# final.net
KiCad netlist of a schematic drawn in EAGLE
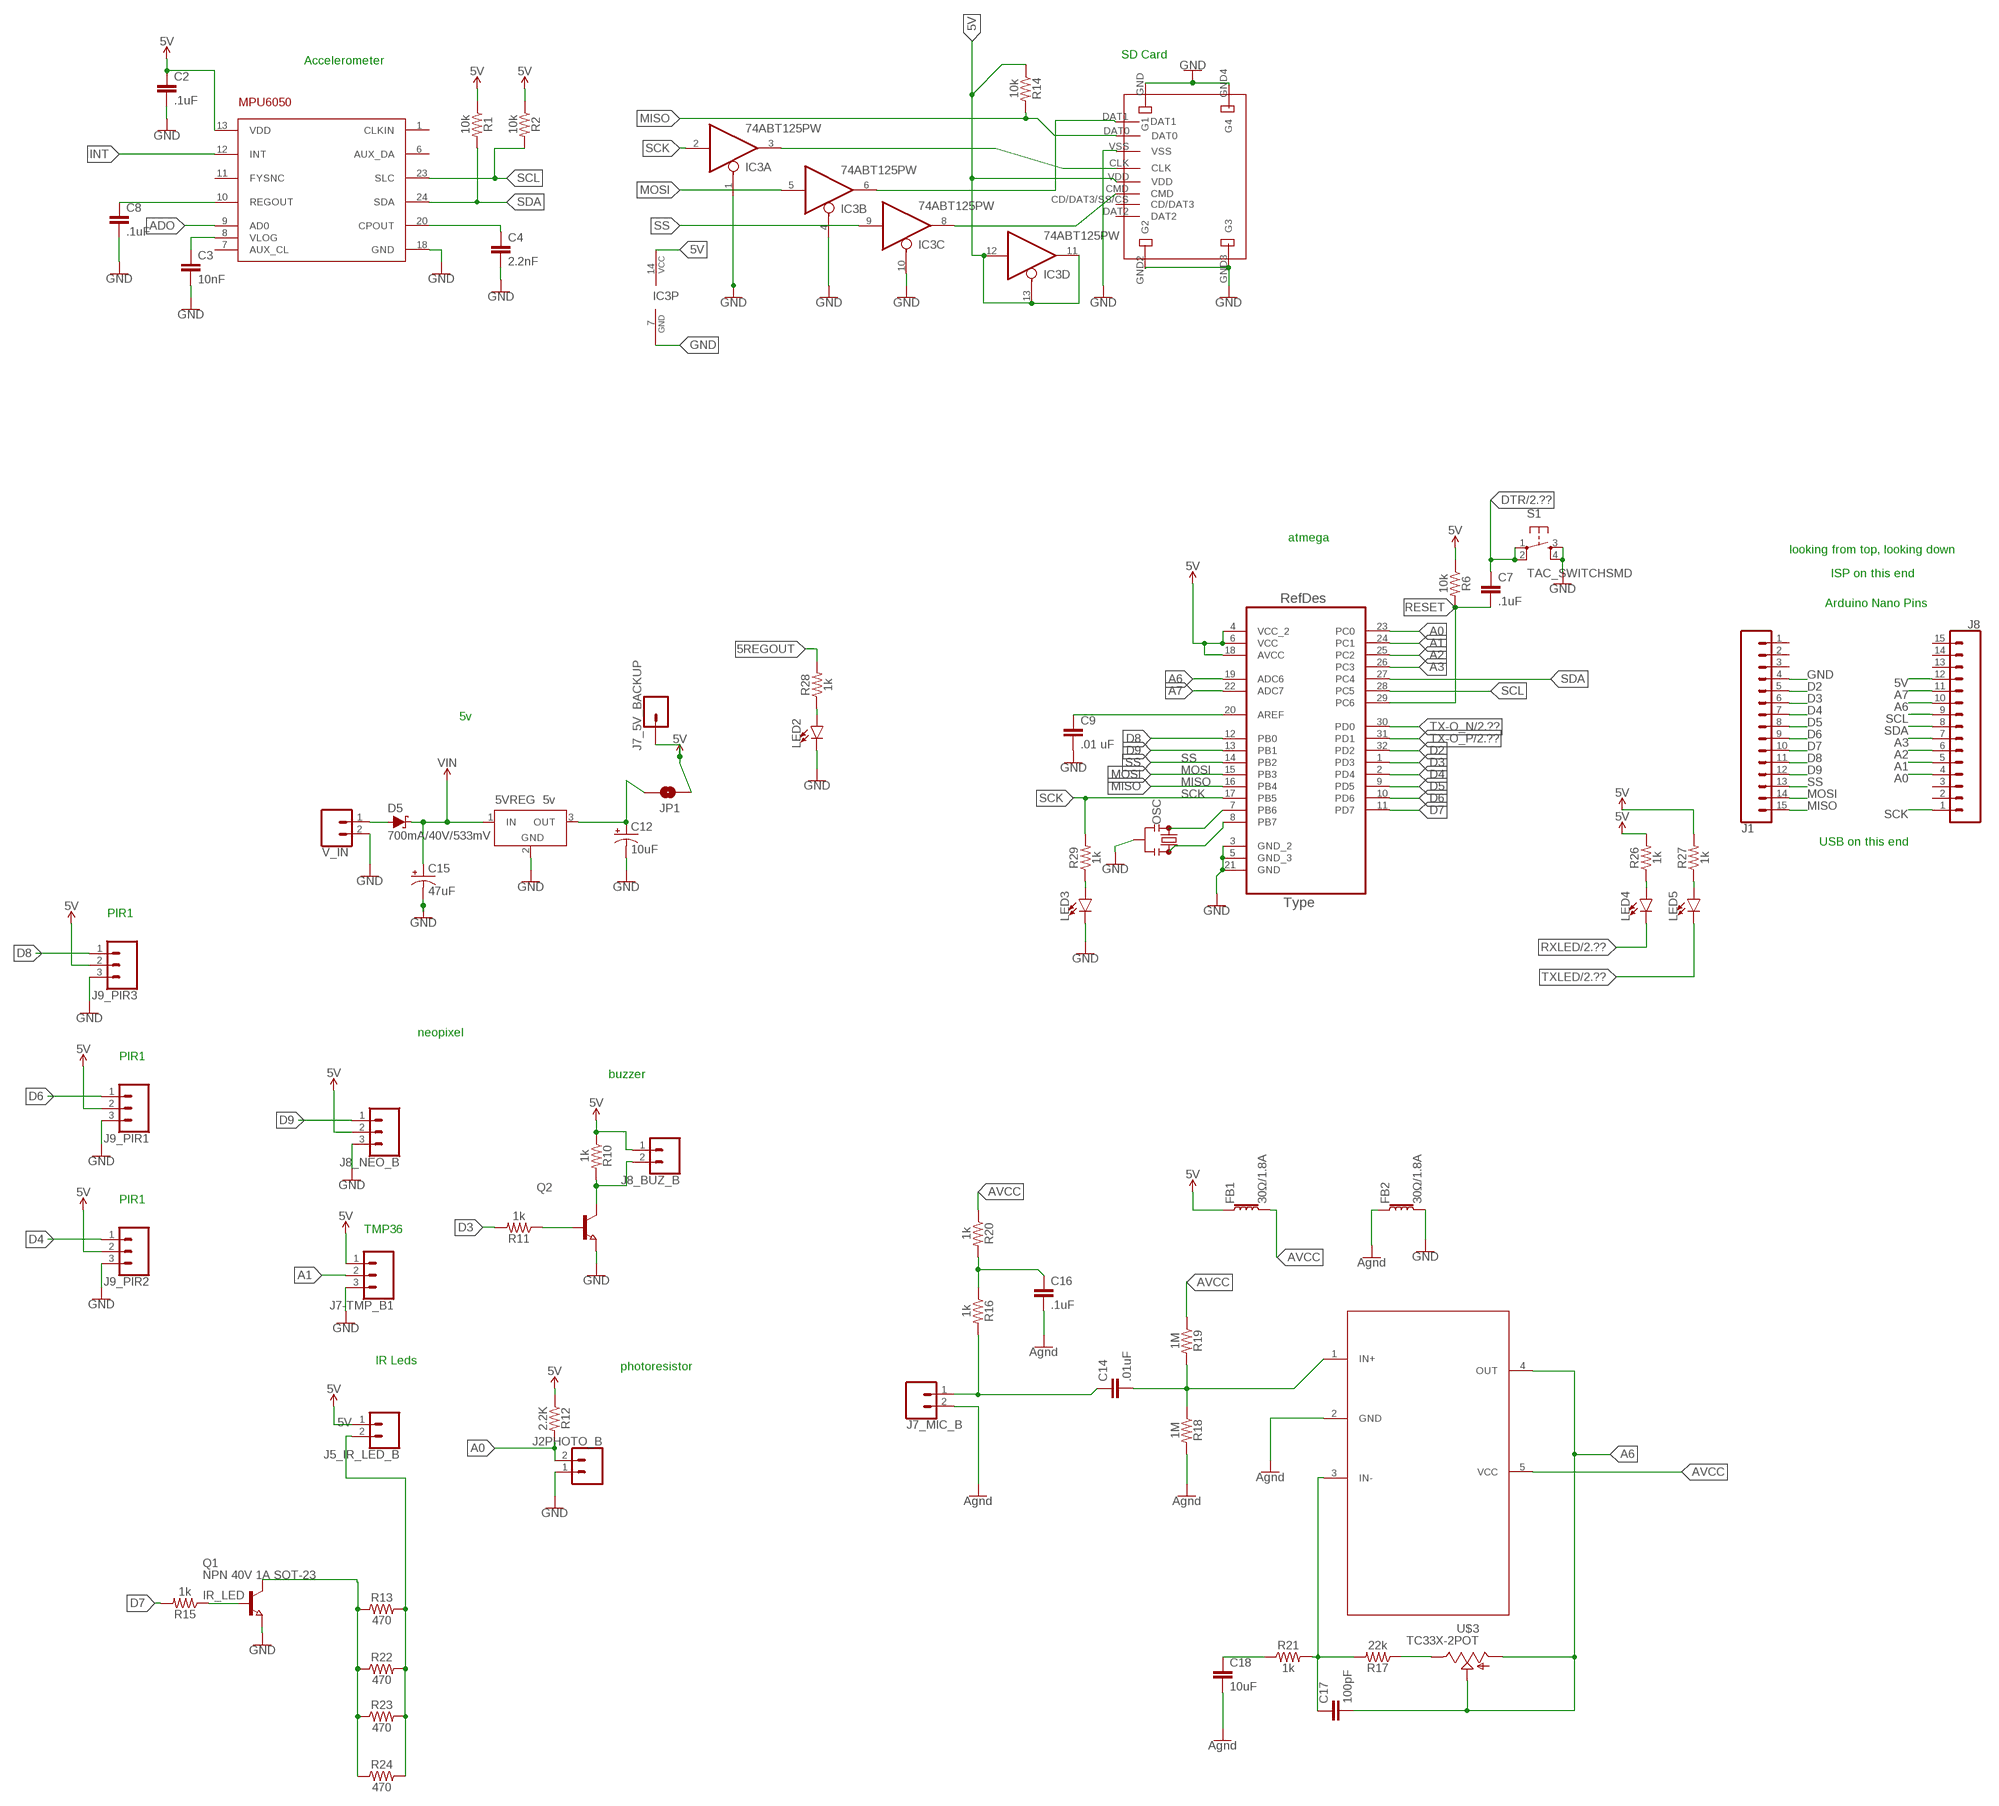
[diagram p0: schematic, sheet 1]
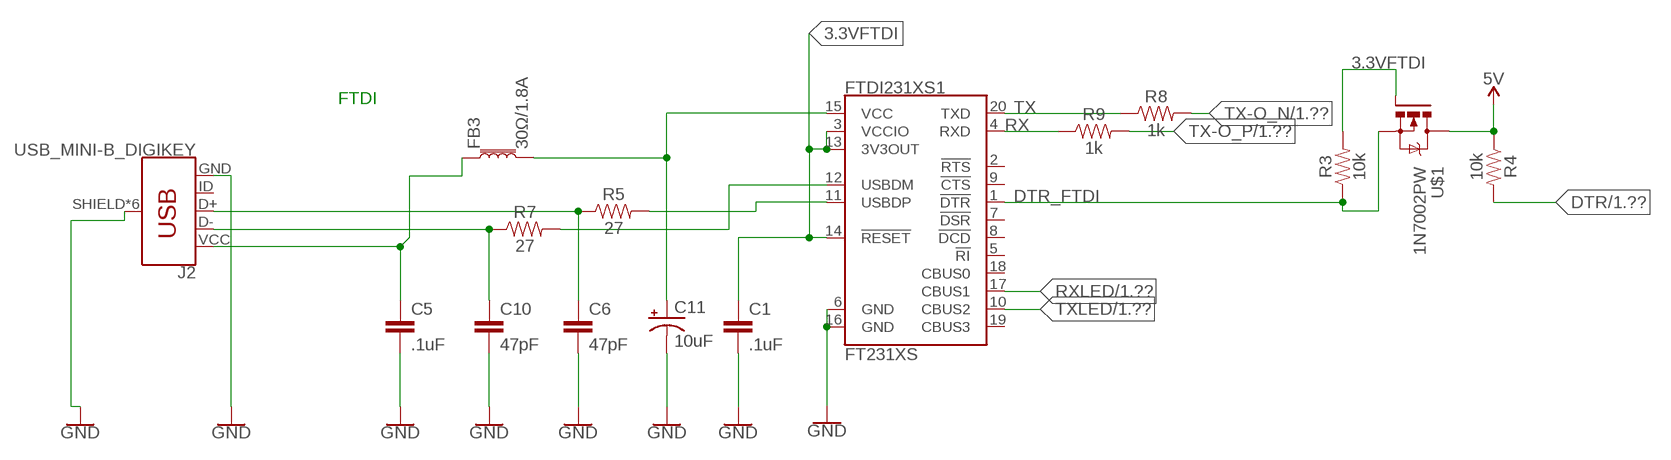
[diagram p1: schematic, sheet 2]

(export (version "E")
  (design (tool "Eeschema 10.0.6"))
  (components
    (comp (ref "C1")
      (value ".1uF")
      (footprint "eagle-import:0402-CAP")
      (libsource (lib "eagle-import") (part ".22UF-CER"))
    )
    (comp (ref "C5")
      (value ".1uF")
      (footprint "eagle-import:0402-CAP")
      (libsource (lib "eagle-import") (part ".22UF-CER"))
    )
    (comp (ref "C6")
      (value "47pF")
      (footprint "eagle-import:0402-CAP")
      (libsource (lib "eagle-import") (part ".22UF-CER"))
    )
    (comp (ref "C10")
      (value "47pF")
      (footprint "eagle-import:0402-CAP")
      (libsource (lib "eagle-import") (part ".22UF-CER"))
    )
    (comp (ref "C11")
      (value "10uF")
      (footprint "eagle-import:EIA3216")
      (libsource (lib "eagle-import") (part "10UF-TANT"))
    )
    (comp (ref "FB3")
      (value "30Ω/1.8A")
      (footprint "eagle-import:0603")
      (libsource (lib "eagle-import") (part "FERRITE_BEAD-0603"))
    )
    (comp (ref "FTDI231XS1")
      (value "FT231XS")
      (footprint "eagle-import:SSOP20_L")
      (libsource (lib "eagle-import") (part "FT231XS"))
    )
    (comp (ref "J2")
      (value "USB_MINI-B_DIGIKEY")
      (footprint "eagle-import:MICRO-USB-DIGIKEY-FCI2")
      (libsource (lib "eagle-import") (part "USB_MINI-B_DIGIKEY"))
    )
    (comp (ref "R3")
      (value "10k")
      (footprint "eagle-import:0603")
      (libsource (lib "eagle-import") (part "0.05OHM-0603-1/5W-1%"))
    )
    (comp (ref "R4")
      (value "10k")
      (footprint "eagle-import:0603")
      (libsource (lib "eagle-import") (part "0.05OHM-0603-1/5W-1%"))
    )
    (comp (ref "R5")
      (value "27")
      (footprint "eagle-import:0603")
      (libsource (lib "eagle-import") (part "0.05OHM-0603-1/5W-1%"))
    )
    (comp (ref "R7")
      (value "27")
      (footprint "eagle-import:0603")
      (libsource (lib "eagle-import") (part "0.05OHM-0603-1/5W-1%"))
    )
    (comp (ref "R8")
      (value "1k")
      (footprint "eagle-import:0603")
      (libsource (lib "eagle-import") (part "0.05OHM-0603-1/5W-1%"))
    )
    (comp (ref "R9")
      (value "1k")
      (footprint "eagle-import:0603")
      (libsource (lib "eagle-import") (part "0.05OHM-0603-1/5W-1%"))
    )
    (comp (ref "U$1")
      (value "1N7002PW")
      (footprint "eagle-import:SOT323W_INFINEON")
      (libsource (lib "eagle-import") (part "1N7002PW"))
    )
    (comp (ref "5VREG")
      (value "5v")
      (footprint "eagle-import:SOT223")
      (fields (field (name "MPN") "LT1129CST-5#PBF"))
      (libsource (lib "eagle-import") (part "LT1129CST5"))
    )
    (comp (ref "ATMEGA328P-AU")
      (value "ATMEGA328P-AU")
      (footprint "eagle-import:QFP80P900X900X120-32N")
      (libsource (lib "eagle-import") (part "ATMEGA328P-AU"))
    )
    (comp (ref "C2")
      (value ".1uF")
      (footprint "eagle-import:0402-CAP")
      (libsource (lib "eagle-import") (part ".22UF-CER"))
    )
    (comp (ref "C3")
      (value "10nF")
      (footprint "eagle-import:0402-CAP")
      (libsource (lib "eagle-import") (part ".22UF-CER"))
    )
    (comp (ref "C4")
      (value "2.2nF")
      (footprint "eagle-import:0402-CAP")
      (libsource (lib "eagle-import") (part ".22UF-CER"))
    )
    (comp (ref "C7")
      (value ".1uF")
      (footprint "eagle-import:0402-CAP")
      (libsource (lib "eagle-import") (part ".22UF-CER"))
    )
    (comp (ref "C8")
      (value ".1uF")
      (footprint "eagle-import:0402-CAP")
      (libsource (lib "eagle-import") (part ".22UF-CER"))
    )
    (comp (ref "C9")
      (value ".01 uF")
      (footprint "eagle-import:0402-CAP")
      (libsource (lib "eagle-import") (part ".22UF-CER"))
    )
    (comp (ref "C12")
      (value "10uF")
      (footprint "eagle-import:EIA3216")
      (libsource (lib "eagle-import") (part "10UF-TANT"))
    )
    (comp (ref "C14")
      (value ".01uF")
      (footprint "eagle-import:0402-CAP")
      (libsource (lib "eagle-import") (part ".22UF-CER"))
    )
    (comp (ref "C15")
      (value "47uF")
      (footprint "eagle-import:EIA3216")
      (libsource (lib "eagle-import") (part "10UF-TANT"))
    )
    (comp (ref "C16")
      (value ".1uF")
      (footprint "eagle-import:0402-CAP")
      (libsource (lib "eagle-import") (part ".22UF-CER"))
    )
    (comp (ref "C17")
      (value "100pF")
      (footprint "eagle-import:0402-CAP")
      (libsource (lib "eagle-import") (part ".22UF-CER"))
    )
    (comp (ref "C18")
      (value "10uF")
      (footprint "eagle-import:0402-CAP")
      (libsource (lib "eagle-import") (part ".22UF-CER"))
    )
    (comp (ref "D5")
      (value "700mA/40V/533mV")
      (footprint "eagle-import:SOT23-3")
      (libsource (lib "eagle-import") (part "DIODE-SCHOTTKY-ZLLS500"))
    )
    (comp (ref "FB1")
      (value "30Ω/1.8A")
      (footprint "eagle-import:0603")
      (libsource (lib "eagle-import") (part "FERRITE_BEAD-0603"))
    )
    (comp (ref "FB2")
      (value "30Ω/1.8A")
      (footprint "eagle-import:0603")
      (libsource (lib "eagle-import") (part "FERRITE_BEAD-0603"))
    )
    (comp (ref "IC3")
      (value "74ABT125PW")
      (footprint "eagle-import:TSSOP14")
      (libsource (lib "eagle-import") (part "74125PWABT"))
    )
    (comp (ref "IC4")
      (value "MAX4466KS")
      (footprint "eagle-import:SC70-5")
      (libsource (lib "eagle-import") (part "MAX4466KS"))
    )
    (comp (ref "J1")
      (value "CONN_15")
      (footprint "eagle-import:1X15")
      (libsource (lib "eagle-import") (part "CONN_15"))
    )
    (comp (ref "J2PHOTO_B")
      (value "CONN_02LOCK")
      (footprint "eagle-import:1X02_LOCK")
      (libsource (lib "eagle-import") (part "CONN_02LOCK"))
    )
    (comp (ref "J5_IR_LED_B")
      (value "CONN_02LOCK")
      (footprint "eagle-import:1X02_LOCK")
      (libsource (lib "eagle-import") (part "CONN_02LOCK"))
    )
    (comp (ref "J7-TMP_B1")
      (value "CONN_03")
      (footprint "eagle-import:1X03")
      (libsource (lib "eagle-import") (part "CONN_03"))
    )
    (comp (ref "J7_5V_BACKUP")
      (value "CONN_01")
      (footprint "eagle-import:1X01")
      (libsource (lib "eagle-import") (part "CONN_01"))
    )
    (comp (ref "J7_MIC_B")
      (value "CONN_02LOCK")
      (footprint "eagle-import:1X02_LOCK")
      (libsource (lib "eagle-import") (part "CONN_02LOCK"))
    )
    (comp (ref "J8")
      (value "CONN_15")
      (footprint "eagle-import:1X15")
      (libsource (lib "eagle-import") (part "CONN_15"))
    )
    (comp (ref "J8_BUZ_B")
      (value "CONN_02LOCK")
      (footprint "eagle-import:1X02_LOCK")
      (libsource (lib "eagle-import") (part "CONN_02LOCK"))
    )
    (comp (ref "J8_NEO_B")
      (value "CONN_03")
      (footprint "eagle-import:1X03")
      (libsource (lib "eagle-import") (part "CONN_03"))
    )
    (comp (ref "J9_PIR1")
      (value "CONN_03")
      (footprint "eagle-import:1X03")
      (libsource (lib "eagle-import") (part "CONN_03"))
    )
    (comp (ref "J9_PIR2")
      (value "CONN_03")
      (footprint "eagle-import:1X03")
      (libsource (lib "eagle-import") (part "CONN_03"))
    )
    (comp (ref "J9_PIR3")
      (value "CONN_03")
      (footprint "eagle-import:1X03")
      (libsource (lib "eagle-import") (part "CONN_03"))
    )
    (comp (ref "JP1")
      (value "JUMPER-SMT_2_NO_NO-SILK_ROUND")
      (footprint "eagle-import:SMT-JUMPER_2_NO_NO-SILK_ROUND")
      (libsource (lib "eagle-import") (part "JUMPER-SMT_2_NO_NO-SILK_ROUND"))
    )
    (comp (ref "LED2")
      (value "LED0603")
      (footprint "eagle-import:LED-0603")
      (libsource (lib "eagle-import") (part "LED0603"))
    )
    (comp (ref "LED3")
      (value "LED0603")
      (footprint "eagle-import:LED-0603")
      (libsource (lib "eagle-import") (part "LED0603"))
    )
    (comp (ref "LED4")
      (value "LED0603")
      (footprint "eagle-import:LED-0603")
      (libsource (lib "eagle-import") (part "LED0603"))
    )
    (comp (ref "LED5")
      (value "LED0603")
      (footprint "eagle-import:LED-0603")
      (libsource (lib "eagle-import") (part "LED0603"))
    )
    (comp (ref "MPU6050")
      (value "MPU-6050")
      (footprint "eagle-import:QFN24-4X4")
      (libsource (lib "eagle-import") (part "MPU-6050"))
    )
    (comp (ref "OSC")
      (value "RESONATORSMD-3.2X1.3")
      (footprint "eagle-import:RESONATOR-SMD-3.2X1.3")
      (libsource (lib "eagle-import") (part "RESONATORSMD-3.2X1.3"))
    )
    (comp (ref "Q1")
      (value "NPN 40V 1A SOT-23")
      (footprint "eagle-import:SOT23")
      (libsource (lib "eagle-import") (part "NPN-TRANSISTOR_SOT23"))
    )
    (comp (ref "Q2")
      (value "NPN-TRANSISTOR_SOT23")
      (footprint "eagle-import:SOT23")
      (libsource (lib "eagle-import") (part "NPN-TRANSISTOR_SOT23"))
    )
    (comp (ref "R1")
      (value "10k")
      (footprint "eagle-import:0603")
      (libsource (lib "eagle-import") (part "0.05OHM-0603-1/5W-1%"))
    )
    (comp (ref "R2")
      (value "10k")
      (footprint "eagle-import:0603")
      (libsource (lib "eagle-import") (part "0.05OHM-0603-1/5W-1%"))
    )
    (comp (ref "R6")
      (value "10k")
      (footprint "eagle-import:0603")
      (libsource (lib "eagle-import") (part "0.05OHM-0603-1/5W-1%"))
    )
    (comp (ref "R10")
      (value "1k")
      (footprint "eagle-import:0603")
      (libsource (lib "eagle-import") (part "0.05OHM-0603-1/5W-1%"))
    )
    (comp (ref "R11")
      (value "1k")
      (footprint "eagle-import:0603")
      (libsource (lib "eagle-import") (part "0.05OHM-0603-1/5W-1%"))
    )
    (comp (ref "R12")
      (value "2.2K")
      (footprint "eagle-import:0603")
      (libsource (lib "eagle-import") (part "0.05OHM-0603-1/5W-1%"))
    )
    (comp (ref "R13")
      (value "470")
      (footprint "eagle-import:0603")
      (libsource (lib "eagle-import") (part "2.2MOHM-1/10W-5%(0603)"))
    )
    (comp (ref "R14")
      (value "10k")
      (footprint "eagle-import:0603")
      (libsource (lib "eagle-import") (part "0.05OHM-0603-1/5W-1%"))
    )
    (comp (ref "R15")
      (value "1k")
      (footprint "eagle-import:0603")
      (libsource (lib "eagle-import") (part "0.05OHM-0603-1/5W-1%"))
    )
    (comp (ref "R16")
      (value "1k")
      (footprint "eagle-import:0603")
      (libsource (lib "eagle-import") (part "0.05OHM-0603-1/5W-1%"))
    )
    (comp (ref "R17")
      (value "22k")
      (footprint "eagle-import:0603")
      (libsource (lib "eagle-import") (part "0.05OHM-0603-1/5W-1%"))
    )
    (comp (ref "R18")
      (value "1M")
      (footprint "eagle-import:0603")
      (libsource (lib "eagle-import") (part "0.05OHM-0603-1/5W-1%"))
    )
    (comp (ref "R19")
      (value "1M")
      (footprint "eagle-import:0603")
      (libsource (lib "eagle-import") (part "0.05OHM-0603-1/5W-1%"))
    )
    (comp (ref "R20")
      (value "1k")
      (footprint "eagle-import:0603")
      (libsource (lib "eagle-import") (part "0.05OHM-0603-1/5W-1%"))
    )
    (comp (ref "R21")
      (value "1k")
      (footprint "eagle-import:0603")
      (libsource (lib "eagle-import") (part "0.05OHM-0603-1/5W-1%"))
    )
    (comp (ref "R22")
      (value "470")
      (footprint "eagle-import:0603")
      (libsource (lib "eagle-import") (part "2.2MOHM-1/10W-5%(0603)"))
    )
    (comp (ref "R23")
      (value "470")
      (footprint "eagle-import:0603")
      (libsource (lib "eagle-import") (part "2.2MOHM-1/10W-5%(0603)"))
    )
    (comp (ref "R24")
      (value "470")
      (footprint "eagle-import:0603")
      (libsource (lib "eagle-import") (part "2.2MOHM-1/10W-5%(0603)"))
    )
    (comp (ref "R26")
      (value "1k")
      (footprint "eagle-import:0603")
      (libsource (lib "eagle-import") (part "2.2MOHM-1/10W-5%(0603)"))
    )
    (comp (ref "R27")
      (value "1k")
      (footprint "eagle-import:0603")
      (libsource (lib "eagle-import") (part "2.2MOHM-1/10W-5%(0603)"))
    )
    (comp (ref "R28")
      (value "1k")
      (footprint "eagle-import:0603")
      (libsource (lib "eagle-import") (part "2.2MOHM-1/10W-5%(0603)"))
    )
    (comp (ref "R29")
      (value "1k")
      (footprint "eagle-import:0603")
      (libsource (lib "eagle-import") (part "2.2MOHM-1/10W-5%(0603)"))
    )
    (comp (ref "S1")
      (value "TAC_SWITCHSMD")
      (footprint "eagle-import:TACTILE-SWITCH-SMD")
      (libsource (lib "eagle-import") (part "TAC_SWITCHSMD"))
    )
    (comp (ref "U$2")
      (value "WM6698TR-ND_MICROSD")
      (footprint "eagle-import:MICROSD2")
      (libsource (lib "eagle-import") (part "WM6698TR-ND_MICROSD"))
    )
    (comp (ref "U$3")
      (value "TC33X-2POT")
      (footprint "eagle-import:TC33X-2")
      (libsource (lib "eagle-import") (part "TC33X-2POT"))
    )
    (comp (ref "V_IN")
      (value "CONN_02LOCK")
      (footprint "eagle-import:1X02_LOCK")
      (libsource (lib "eagle-import") (part "CONN_02LOCK"))
    )
  )
  (nets
    (net (code "1") (name "3.3VFTDI") (class "Default")
      (node (ref "C1") (pin "1") (pinfunction "1_1") (pintype "passive"))
      (node (ref "FTDI231XS1") (pin "13") (pinfunction "3V3OUT_13") (pintype "bidirectional"))
      (node (ref "FTDI231XS1") (pin "14") (pinfunction "~{RESET}_14") (pintype "bidirectional"))
      (node (ref "FTDI231XS1") (pin "3") (pinfunction "VCCIO_3") (pintype "bidirectional"))
      (node (ref "R3") (pin "2") (pinfunction "2_2") (pintype "passive"))
      (node (ref "U$1") (pin "1") (pinfunction "G_1") (pintype "passive"))
    )
    (net (code "2") (name "5REGOUT") (class "Default")
      (node (ref "5VREG") (pin "3") (pinfunction "OUT_3") (pintype "output"))
      (node (ref "C12") (pin "A") (pinfunction "+_A") (pintype "passive"))
      (node (ref "JP1") (pin "2") (pinfunction "2_2") (pintype "passive"))
      (node (ref "R28") (pin "2") (pinfunction "2_2") (pintype "passive"))
    )
    (net (code "3") (name "5V") (class "Default")
      (node (ref "ATMEGA328P-AU") (pin "18") (pinfunction "AVCC_18") (pintype "power_in"))
      (node (ref "ATMEGA328P-AU") (pin "4") (pinfunction "VCC_2_4") (pintype "power_in"))
      (node (ref "ATMEGA328P-AU") (pin "6") (pinfunction "VCC_6") (pintype "power_in"))
      (node (ref "C2") (pin "1") (pinfunction "1_1") (pintype "passive"))
      (node (ref "FB1") (pin "1") (pinfunction "1_1") (pintype "passive"))
      (node (ref "IC3") (pin "11") (pinfunction "O_11") (pintype "tri_state"))
      (node (ref "IC3") (pin "12") (pinfunction "I_12") (pintype "input"))
      (node (ref "IC3") (pin "13") (pinfunction "OE_13") (pintype "input"))
      (node (ref "IC3") (pin "14") (pinfunction "VCC_14") (pintype "power_in"))
      (node (ref "J5_IR_LED_B") (pin "1") (pinfunction "1_1") (pintype "passive"))
      (node (ref "J7-TMP_B1") (pin "1") (pinfunction "1_1") (pintype "passive"))
      (node (ref "J7_5V_BACKUP") (pin "1") (pinfunction "1_1") (pintype "passive"))
      (node (ref "J8") (pin "12") (pinfunction "12_12") (pintype "passive"))
      (node (ref "J8_BUZ_B") (pin "1") (pinfunction "1_1") (pintype "passive"))
      (node (ref "J8_NEO_B") (pin "2") (pinfunction "2_2") (pintype "passive"))
      (node (ref "J9_PIR1") (pin "2") (pinfunction "2_2") (pintype "passive"))
      (node (ref "J9_PIR2") (pin "2") (pinfunction "2_2") (pintype "passive"))
      (node (ref "J9_PIR3") (pin "2") (pinfunction "2_2") (pintype "passive"))
      (node (ref "JP1") (pin "1") (pinfunction "1_1") (pintype "passive"))
      (node (ref "MPU6050") (pin "13") (pinfunction "VDD_13") (pintype "bidirectional"))
      (node (ref "R1") (pin "1") (pinfunction "1_1") (pintype "passive"))
      (node (ref "R10") (pin "1") (pinfunction "1_1") (pintype "passive"))
      (node (ref "R12") (pin "1") (pinfunction "1_1") (pintype "passive"))
      (node (ref "R14") (pin "1") (pinfunction "1_1") (pintype "passive"))
      (node (ref "R2") (pin "1") (pinfunction "1_1") (pintype "passive"))
      (node (ref "R26") (pin "2") (pinfunction "2_2") (pintype "passive"))
      (node (ref "R27") (pin "2") (pinfunction "2_2") (pintype "passive"))
      (node (ref "R4") (pin "1") (pinfunction "1_1") (pintype "passive"))
      (node (ref "R6") (pin "1") (pinfunction "1_1") (pintype "passive"))
      (node (ref "U$1") (pin "3") (pinfunction "D_3") (pintype "passive"))
      (node (ref "U$2") (pin "VDD") (pinfunction "VDD_VDD") (pintype "bidirectional"))
    )
    (net (code "4") (name "A0") (class "Default")
      (node (ref "ATMEGA328P-AU") (pin "23") (pinfunction "PC0_23") (pintype "bidirectional"))
      (node (ref "J2PHOTO_B") (pin "2") (pinfunction "2_2") (pintype "passive"))
      (node (ref "J8") (pin "4") (pinfunction "4_4") (pintype "passive"))
      (node (ref "R12") (pin "2") (pinfunction "2_2") (pintype "passive"))
    )
    (net (code "5") (name "A1") (class "Default")
      (node (ref "ATMEGA328P-AU") (pin "24") (pinfunction "PC1_24") (pintype "bidirectional"))
      (node (ref "J7-TMP_B1") (pin "2") (pinfunction "2_2") (pintype "passive"))
      (node (ref "J8") (pin "5") (pinfunction "5_5") (pintype "passive"))
    )
    (net (code "6") (name "A2") (class "Default")
      (node (ref "ATMEGA328P-AU") (pin "25") (pinfunction "PC2_25") (pintype "bidirectional"))
      (node (ref "J8") (pin "6") (pinfunction "6_6") (pintype "passive"))
    )
    (net (code "7") (name "A3") (class "Default")
      (node (ref "ATMEGA328P-AU") (pin "26") (pinfunction "PC3_26") (pintype "bidirectional"))
      (node (ref "J8") (pin "7") (pinfunction "7_7") (pintype "passive"))
    )
    (net (code "8") (name "A6") (class "Default")
      (node (ref "ATMEGA328P-AU") (pin "19") (pinfunction "ADC6_19") (pintype "input"))
      (node (ref "C17") (pin "2") (pinfunction "2_2") (pintype "passive"))
      (node (ref "IC4") (pin "4") (pinfunction "OUT_4") (pintype "bidirectional"))
      (node (ref "J8") (pin "10") (pinfunction "10_10") (pintype "passive"))
      (node (ref "U$3") (pin "2") (pinfunction "2_2") (pintype "passive"))
      (node (ref "U$3") (pin "3") (pinfunction "3_3") (pintype "passive"))
    )
    (net (code "9") (name "A7") (class "Default")
      (node (ref "ATMEGA328P-AU") (pin "22") (pinfunction "ADC7_22") (pintype "input"))
      (node (ref "J8") (pin "11") (pinfunction "11_11") (pintype "passive"))
    )
    (net (code "10") (name "ADO") (class "Default")
      (node (ref "MPU6050") (pin "9") (pinfunction "AD0_9") (pintype "bidirectional"))
    )
    (net (code "11") (name "AVCC") (class "Default")
      (node (ref "FB1") (pin "2") (pinfunction "2_2") (pintype "passive"))
      (node (ref "IC4") (pin "5") (pinfunction "VCC_5") (pintype "bidirectional"))
      (node (ref "R19") (pin "1") (pinfunction "1_1") (pintype "passive"))
      (node (ref "R20") (pin "1") (pinfunction "1_1") (pintype "passive"))
    )
    (net (code "12") (name "D2") (class "Default")
      (node (ref "ATMEGA328P-AU") (pin "32") (pinfunction "PD2_32") (pintype "bidirectional"))
      (node (ref "J1") (pin "5") (pinfunction "5_5") (pintype "passive"))
    )
    (net (code "13") (name "D3") (class "Default")
      (node (ref "ATMEGA328P-AU") (pin "1") (pinfunction "PD3_1") (pintype "bidirectional"))
      (node (ref "J1") (pin "6") (pinfunction "6_6") (pintype "passive"))
      (node (ref "R11") (pin "2") (pinfunction "2_2") (pintype "passive"))
    )
    (net (code "14") (name "D4") (class "Default")
      (node (ref "ATMEGA328P-AU") (pin "2") (pinfunction "PD4_2") (pintype "bidirectional"))
      (node (ref "J1") (pin "7") (pinfunction "7_7") (pintype "passive"))
      (node (ref "J9_PIR2") (pin "1") (pinfunction "1_1") (pintype "passive"))
    )
    (net (code "15") (name "D5") (class "Default")
      (node (ref "ATMEGA328P-AU") (pin "9") (pinfunction "PD5_9") (pintype "bidirectional"))
      (node (ref "J1") (pin "8") (pinfunction "8_8") (pintype "passive"))
    )
    (net (code "16") (name "D6") (class "Default")
      (node (ref "ATMEGA328P-AU") (pin "10") (pinfunction "PD6_10") (pintype "bidirectional"))
      (node (ref "J1") (pin "9") (pinfunction "9_9") (pintype "passive"))
      (node (ref "J9_PIR1") (pin "1") (pinfunction "1_1") (pintype "passive"))
    )
    (net (code "17") (name "D7") (class "Default")
      (node (ref "ATMEGA328P-AU") (pin "11") (pinfunction "PD7_11") (pintype "bidirectional"))
      (node (ref "J1") (pin "10") (pinfunction "10_10") (pintype "passive"))
      (node (ref "R15") (pin "2") (pinfunction "2_2") (pintype "passive"))
    )
    (net (code "18") (name "D8") (class "Default")
      (node (ref "ATMEGA328P-AU") (pin "12") (pinfunction "PB0_12") (pintype "bidirectional"))
      (node (ref "J1") (pin "11") (pinfunction "11_11") (pintype "passive"))
      (node (ref "J9_PIR3") (pin "1") (pinfunction "1_1") (pintype "passive"))
    )
    (net (code "19") (name "D9") (class "Default")
      (node (ref "ATMEGA328P-AU") (pin "13") (pinfunction "PB1_13") (pintype "bidirectional"))
      (node (ref "J1") (pin "12") (pinfunction "12_12") (pintype "passive"))
      (node (ref "J8_NEO_B") (pin "1") (pinfunction "1_1") (pintype "passive"))
    )
    (net (code "20") (name "DTR") (class "Default")
      (node (ref "C7") (pin "1") (pinfunction "1_1") (pintype "passive"))
      (node (ref "R4") (pin "2") (pinfunction "2_2") (pintype "passive"))
      (node (ref "S1") (pin "1") (pinfunction "1_1") (pintype "passive"))
      (node (ref "S1") (pin "2") (pinfunction "2_2") (pintype "passive"))
    )
    (net (code "21") (name "DTR_FTDI") (class "Default")
      (node (ref "FTDI231XS1") (pin "1") (pinfunction "~{DTR}_1") (pintype "bidirectional"))
      (node (ref "R3") (pin "1") (pinfunction "1_1") (pintype "passive"))
      (node (ref "U$1") (pin "2") (pinfunction "S_2") (pintype "passive"))
    )
    (net (code "22") (name "GND") (class "Default")
      (node (ref "5VREG") (pin "2") (pinfunction "GND_2") (pintype "power_in"))
      (node (ref "ATMEGA328P-AU") (pin "21") (pinfunction "GND_21") (pintype "passive"))
      (node (ref "ATMEGA328P-AU") (pin "3") (pinfunction "GND_2_3") (pintype "passive"))
      (node (ref "ATMEGA328P-AU") (pin "5") (pinfunction "GND_3_5") (pintype "passive"))
      (node (ref "C1") (pin "2") (pinfunction "2_2") (pintype "passive"))
      (node (ref "C10") (pin "2") (pinfunction "2_2") (pintype "passive"))
      (node (ref "C11") (pin "C") (pinfunction "-_C") (pintype "passive"))
      (node (ref "C12") (pin "C") (pinfunction "-_C") (pintype "passive"))
      (node (ref "C15") (pin "C") (pinfunction "-_C") (pintype "passive"))
      (node (ref "C16") (pin "2") (pinfunction "2_2") (pintype "passive"))
      (node (ref "C18") (pin "2") (pinfunction "2_2") (pintype "passive"))
      (node (ref "C2") (pin "2") (pinfunction "2_2") (pintype "passive"))
      (node (ref "C3") (pin "2") (pinfunction "2_2") (pintype "passive"))
      (node (ref "C4") (pin "2") (pinfunction "2_2") (pintype "passive"))
      (node (ref "C5") (pin "2") (pinfunction "2_2") (pintype "passive"))
      (node (ref "C6") (pin "2") (pinfunction "2_2") (pintype "passive"))
      (node (ref "C8") (pin "2") (pinfunction "2_2") (pintype "passive"))
      (node (ref "C9") (pin "2") (pinfunction "2_2") (pintype "passive"))
      (node (ref "FB2") (pin "1") (pinfunction "1_1") (pintype "passive"))
      (node (ref "FB2") (pin "2") (pinfunction "2_2") (pintype "passive"))
      (node (ref "FTDI231XS1") (pin "16") (pinfunction "GND_16") (pintype "bidirectional"))
      (node (ref "FTDI231XS1") (pin "6") (pinfunction "GND_6") (pintype "bidirectional"))
      (node (ref "IC3") (pin "1") (pinfunction "OE_1") (pintype "input"))
      (node (ref "IC3") (pin "10") (pinfunction "OE_10") (pintype "input"))
      (node (ref "IC3") (pin "4") (pinfunction "OE_4") (pintype "input"))
      (node (ref "IC3") (pin "7") (pinfunction "GND_7") (pintype "power_in"))
      (node (ref "IC4") (pin "2") (pinfunction "GND_2") (pintype "bidirectional"))
      (node (ref "J1") (pin "4") (pinfunction "4_4") (pintype "passive"))
      (node (ref "J2") (pin "GND") (pinfunction "GND_GND") (pintype "power_in"))
      (node (ref "J2") (pin "SHIELD") (pinfunction "SHIELD_SHIELD") (pintype "bidirectional"))
      (node (ref "J2") (pin "SHIELD1") (pinfunction "SHIELD_SHIELD1") (pintype "bidirectional"))
      (node (ref "J2") (pin "SHIELD2") (pinfunction "SHIELD_SHIELD2") (pintype "bidirectional"))
      (node (ref "J2") (pin "SHIELD3") (pinfunction "SHIELD_SHIELD3") (pintype "bidirectional"))
      (node (ref "J2") (pin "SHIELD4") (pinfunction "SHIELD_SHIELD4") (pintype "bidirectional"))
      (node (ref "J2") (pin "SHIELD5") (pinfunction "SHIELD_SHIELD5") (pintype "bidirectional"))
      (node (ref "J2PHOTO_B") (pin "1") (pinfunction "1_1") (pintype "passive"))
      (node (ref "J7-TMP_B1") (pin "3") (pinfunction "3_3") (pintype "passive"))
      (node (ref "J7_MIC_B") (pin "2") (pinfunction "2_2") (pintype "passive"))
      (node (ref "J8_NEO_B") (pin "3") (pinfunction "3_3") (pintype "passive"))
      (node (ref "J9_PIR1") (pin "3") (pinfunction "3_3") (pintype "passive"))
      (node (ref "J9_PIR2") (pin "3") (pinfunction "3_3") (pintype "passive"))
      (node (ref "J9_PIR3") (pin "3") (pinfunction "3_3") (pintype "passive"))
      (node (ref "LED2") (pin "C") (pinfunction "C_C") (pintype "passive"))
      (node (ref "LED3") (pin "C") (pinfunction "C_C") (pintype "passive"))
      (node (ref "MPU6050") (pin "18") (pinfunction "GND_18") (pintype "bidirectional"))
      (node (ref "OSC") (pin "2") (pinfunction "2_2") (pintype "passive"))
      (node (ref "Q1") (pin "2") (pinfunction "E_2") (pintype "passive"))
      (node (ref "Q2") (pin "2") (pinfunction "E_2") (pintype "passive"))
      (node (ref "R18") (pin "2") (pinfunction "2_2") (pintype "passive"))
      (node (ref "S1") (pin "3") (pinfunction "3_3") (pintype "passive"))
      (node (ref "S1") (pin "4") (pinfunction "4_4") (pintype "passive"))
      (node (ref "U$2") (pin "GND") (pinfunction "G1_GND") (pintype "bidirectional"))
      (node (ref "U$2") (pin "GND2") (pinfunction "G2_GND2") (pintype "bidirectional"))
      (node (ref "U$2") (pin "GND3") (pinfunction "G3_GND3") (pintype "bidirectional"))
      (node (ref "U$2") (pin "GND4") (pinfunction "G4_GND4") (pintype "bidirectional"))
      (node (ref "U$2") (pin "VSS") (pinfunction "VSS_VSS") (pintype "bidirectional"))
      (node (ref "V_IN") (pin "2") (pinfunction "2_2") (pintype "passive"))
    )
    (net (code "23") (name "INT") (class "Default")
      (node (ref "MPU6050") (pin "12") (pinfunction "INT_12") (pintype "bidirectional"))
    )
    (net (code "24") (name "IR_LED") (class "Default")
      (node (ref "Q1") (pin "1") (pinfunction "B_1") (pintype "passive"))
      (node (ref "R15") (pin "1") (pinfunction "1_1") (pintype "passive"))
    )
    (net (code "25") (name "MISO") (class "Default")
      (node (ref "ATMEGA328P-AU") (pin "16") (pinfunction "PB4_16") (pintype "bidirectional"))
      (node (ref "J1") (pin "15") (pinfunction "15_15") (pintype "passive"))
      (node (ref "R14") (pin "2") (pinfunction "2_2") (pintype "passive"))
      (node (ref "U$2") (pin "DAT0") (pinfunction "DAT0_DAT0") (pintype "bidirectional"))
    )
    (net (code "26") (name "MOSI") (class "Default")
      (node (ref "ATMEGA328P-AU") (pin "15") (pinfunction "PB3_15") (pintype "bidirectional"))
      (node (ref "IC3") (pin "5") (pinfunction "I_5") (pintype "input"))
      (node (ref "J1") (pin "14") (pinfunction "14_14") (pintype "passive"))
    )
    (net (code "27") (name "Net-(ATMEGA328P-AU-AREF)") (class "Default")
      (node (ref "ATMEGA328P-AU") (pin "20") (pinfunction "AREF_20") (pintype "input"))
      (node (ref "C9") (pin "1") (pinfunction "1_1") (pintype "passive"))
    )
    (net (code "28") (name "Net-(ATMEGA328P-AU-PB6)") (class "Default")
      (node (ref "ATMEGA328P-AU") (pin "7") (pinfunction "PB6_7") (pintype "bidirectional"))
      (node (ref "OSC") (pin "1") (pinfunction "1_1") (pintype "passive"))
    )
    (net (code "29") (name "Net-(ATMEGA328P-AU-PB7)") (class "Default")
      (node (ref "ATMEGA328P-AU") (pin "8") (pinfunction "PB7_8") (pintype "bidirectional"))
      (node (ref "OSC") (pin "3") (pinfunction "3_3") (pintype "passive"))
    )
    (net (code "30") (name "Net-(C6-Pad1)") (class "Default")
      (node (ref "C6") (pin "1") (pinfunction "1_1") (pintype "passive"))
      (node (ref "J2") (pin "D+") (pinfunction "D+_D+") (pintype "bidirectional"))
      (node (ref "R5") (pin "1") (pinfunction "1_1") (pintype "passive"))
    )
    (net (code "31") (name "Net-(C10-Pad1)") (class "Default")
      (node (ref "C10") (pin "1") (pinfunction "1_1") (pintype "passive"))
      (node (ref "J2") (pin "D-") (pinfunction "D-_D-") (pintype "bidirectional"))
      (node (ref "R7") (pin "1") (pinfunction "1_1") (pintype "passive"))
    )
    (net (code "32") (name "Net-(C14-Pad1)") (class "Default")
      (node (ref "C14") (pin "1") (pinfunction "1_1") (pintype "passive"))
      (node (ref "J7_MIC_B") (pin "1") (pinfunction "1_1") (pintype "passive"))
      (node (ref "R16") (pin "2") (pinfunction "2_2") (pintype "passive"))
    )
    (net (code "33") (name "Net-(C16-Pad1)") (class "Default")
      (node (ref "C16") (pin "1") (pinfunction "1_1") (pintype "passive"))
      (node (ref "R16") (pin "1") (pinfunction "1_1") (pintype "passive"))
      (node (ref "R20") (pin "2") (pinfunction "2_2") (pintype "passive"))
    )
    (net (code "34") (name "Net-(C18-Pad1)") (class "Default")
      (node (ref "C18") (pin "1") (pinfunction "1_1") (pintype "passive"))
      (node (ref "R21") (pin "1") (pinfunction "1_1") (pintype "passive"))
    )
    (net (code "35") (name "Net-(D5-A)") (class "Default")
      (node (ref "D5") (pin "1") (pinfunction "A_1") (pintype "passive"))
      (node (ref "V_IN") (pin "1") (pinfunction "1_1") (pintype "passive"))
    )
    (net (code "36") (name "Net-(FTDI231XS1-USBDM)") (class "Default")
      (node (ref "FTDI231XS1") (pin "12") (pinfunction "USBDM_12") (pintype "bidirectional"))
      (node (ref "R7") (pin "2") (pinfunction "2_2") (pintype "passive"))
    )
    (net (code "37") (name "Net-(FTDI231XS1-USBDP)") (class "Default")
      (node (ref "FTDI231XS1") (pin "11") (pinfunction "USBDP_11") (pintype "bidirectional"))
      (node (ref "R5") (pin "2") (pinfunction "2_2") (pintype "passive"))
    )
    (net (code "38") (name "Net-(IC3A-O)") (class "Default")
      (node (ref "IC3") (pin "3") (pinfunction "O_3") (pintype "tri_state"))
      (node (ref "U$2") (pin "CLK") (pinfunction "CLK_CLK") (pintype "bidirectional"))
    )
    (net (code "39") (name "Net-(IC3B-O)") (class "Default")
      (node (ref "IC3") (pin "6") (pinfunction "O_6") (pintype "tri_state"))
      (node (ref "U$2") (pin "DAT1") (pinfunction "DAT1_DAT1") (pintype "bidirectional"))
    )
    (net (code "40") (name "Net-(IC3C-O)") (class "Default")
      (node (ref "IC3") (pin "8") (pinfunction "O_8") (pintype "tri_state"))
      (node (ref "U$2") (pin "CMD") (pinfunction "CMD_CMD") (pintype "bidirectional"))
    )
    (net (code "41") (name "Net-(IC4-IN+)") (class "Default")
      (node (ref "C14") (pin "2") (pinfunction "2_2") (pintype "passive"))
      (node (ref "IC4") (pin "1") (pinfunction "IN+_1") (pintype "bidirectional"))
      (node (ref "R18") (pin "1") (pinfunction "1_1") (pintype "passive"))
      (node (ref "R19") (pin "2") (pinfunction "2_2") (pintype "passive"))
    )
    (net (code "42") (name "Net-(IC4-IN-)") (class "Default")
      (node (ref "C17") (pin "1") (pinfunction "1_1") (pintype "passive"))
      (node (ref "IC4") (pin "3") (pinfunction "IN-_3") (pintype "bidirectional"))
      (node (ref "R17") (pin "2") (pinfunction "2_2") (pintype "passive"))
      (node (ref "R21") (pin "2") (pinfunction "2_2") (pintype "passive"))
    )
    (net (code "43") (name "Net-(J5_IR_LED_B-Pad2)") (class "Default")
      (node (ref "J5_IR_LED_B") (pin "2") (pinfunction "2_2") (pintype "passive"))
      (node (ref "R13") (pin "2") (pinfunction "2_2") (pintype "passive"))
      (node (ref "R22") (pin "2") (pinfunction "2_2") (pintype "passive"))
      (node (ref "R23") (pin "2") (pinfunction "2_2") (pintype "passive"))
      (node (ref "R24") (pin "2") (pinfunction "2_2") (pintype "passive"))
    )
    (net (code "44") (name "Net-(LED2-PadA)") (class "Default")
      (node (ref "LED2") (pin "A") (pinfunction "A_A") (pintype "passive"))
      (node (ref "R28") (pin "1") (pinfunction "1_1") (pintype "passive"))
    )
    (net (code "45") (name "Net-(LED3-PadA)") (class "Default")
      (node (ref "LED3") (pin "A") (pinfunction "A_A") (pintype "passive"))
      (node (ref "R29") (pin "1") (pinfunction "1_1") (pintype "passive"))
    )
    (net (code "46") (name "Net-(LED4-PadA)") (class "Default")
      (node (ref "LED4") (pin "A") (pinfunction "A_A") (pintype "passive"))
      (node (ref "R26") (pin "1") (pinfunction "1_1") (pintype "passive"))
    )
    (net (code "47") (name "Net-(LED5-PadA)") (class "Default")
      (node (ref "LED5") (pin "A") (pinfunction "A_A") (pintype "passive"))
      (node (ref "R27") (pin "1") (pinfunction "1_1") (pintype "passive"))
    )
    (net (code "48") (name "Net-(MPU6050-CPOUT)") (class "Default")
      (node (ref "C4") (pin "1") (pinfunction "1_1") (pintype "passive"))
      (node (ref "MPU6050") (pin "20") (pinfunction "CPOUT_20") (pintype "bidirectional"))
    )
    (net (code "49") (name "Net-(MPU6050-REGOUT)") (class "Default")
      (node (ref "C8") (pin "1") (pinfunction "1_1") (pintype "passive"))
      (node (ref "MPU6050") (pin "10") (pinfunction "REGOUT_10") (pintype "bidirectional"))
    )
    (net (code "50") (name "Net-(MPU6050-VLOG)") (class "Default")
      (node (ref "C3") (pin "1") (pinfunction "1_1") (pintype "passive"))
      (node (ref "MPU6050") (pin "8") (pinfunction "VLOG_8") (pintype "bidirectional"))
    )
    (net (code "51") (name "Net-(Q1-C)") (class "Default")
      (node (ref "Q1") (pin "3") (pinfunction "C_3") (pintype "passive"))
      (node (ref "R13") (pin "1") (pinfunction "1_1") (pintype "passive"))
      (node (ref "R22") (pin "1") (pinfunction "1_1") (pintype "passive"))
      (node (ref "R23") (pin "1") (pinfunction "1_1") (pintype "passive"))
      (node (ref "R24") (pin "1") (pinfunction "1_1") (pintype "passive"))
    )
    (net (code "52") (name "Net-(Q2-B)") (class "Default")
      (node (ref "Q2") (pin "1") (pinfunction "B_1") (pintype "passive"))
      (node (ref "R11") (pin "1") (pinfunction "1_1") (pintype "passive"))
    )
    (net (code "53") (name "Net-(Q2-C)") (class "Default")
      (node (ref "J8_BUZ_B") (pin "2") (pinfunction "2_2") (pintype "passive"))
      (node (ref "Q2") (pin "3") (pinfunction "C_3") (pintype "passive"))
      (node (ref "R10") (pin "2") (pinfunction "2_2") (pintype "passive"))
    )
    (net (code "54") (name "Net-(R17-Pad1)") (class "Default")
      (node (ref "R17") (pin "1") (pinfunction "1_1") (pintype "passive"))
      (node (ref "U$3") (pin "1") (pinfunction "1_1") (pintype "passive"))
    )
    (net (code "55") (name "RESET") (class "Default")
      (node (ref "ATMEGA328P-AU") (pin "29") (pinfunction "PC6_29") (pintype "bidirectional"))
      (node (ref "C7") (pin "2") (pinfunction "2_2") (pintype "passive"))
      (node (ref "R6") (pin "2") (pinfunction "2_2") (pintype "passive"))
    )
    (net (code "56") (name "RX") (class "Default")
      (node (ref "FTDI231XS1") (pin "4") (pinfunction "RXD_4") (pintype "bidirectional"))
      (node (ref "R9") (pin "1") (pinfunction "1_1") (pintype "passive"))
    )
    (net (code "57") (name "RXLED") (class "Default")
      (node (ref "FTDI231XS1") (pin "17") (pinfunction "CBUS1_17") (pintype "bidirectional"))
      (node (ref "LED4") (pin "C") (pinfunction "C_C") (pintype "passive"))
    )
    (net (code "58") (name "SCK") (class "Default")
      (node (ref "ATMEGA328P-AU") (pin "17") (pinfunction "PB5_17") (pintype "bidirectional"))
      (node (ref "IC3") (pin "2") (pinfunction "I_2") (pintype "input"))
      (node (ref "J8") (pin "1") (pinfunction "1_1") (pintype "passive"))
      (node (ref "R29") (pin "2") (pinfunction "2_2") (pintype "passive"))
    )
    (net (code "59") (name "SCL") (class "Default")
      (node (ref "ATMEGA328P-AU") (pin "28") (pinfunction "PC5_28") (pintype "bidirectional"))
      (node (ref "J8") (pin "9") (pinfunction "9_9") (pintype "passive"))
      (node (ref "MPU6050") (pin "23") (pinfunction "SLC_23") (pintype "bidirectional"))
      (node (ref "R2") (pin "2") (pinfunction "2_2") (pintype "passive"))
    )
    (net (code "60") (name "SDA") (class "Default")
      (node (ref "ATMEGA328P-AU") (pin "27") (pinfunction "PC4_27") (pintype "bidirectional"))
      (node (ref "J8") (pin "8") (pinfunction "8_8") (pintype "passive"))
      (node (ref "MPU6050") (pin "24") (pinfunction "SDA_24") (pintype "bidirectional"))
      (node (ref "R1") (pin "2") (pinfunction "2_2") (pintype "passive"))
    )
    (net (code "61") (name "SS") (class "Default")
      (node (ref "ATMEGA328P-AU") (pin "14") (pinfunction "PB2_14") (pintype "bidirectional"))
      (node (ref "IC3") (pin "9") (pinfunction "I_9") (pintype "input"))
      (node (ref "J1") (pin "13") (pinfunction "13_13") (pintype "passive"))
    )
    (net (code "62") (name "TX") (class "Default")
      (node (ref "FTDI231XS1") (pin "20") (pinfunction "TXD_20") (pintype "bidirectional"))
      (node (ref "R8") (pin "1") (pinfunction "1_1") (pintype "passive"))
    )
    (net (code "63") (name "TX-O_N") (class "Default")
      (node (ref "ATMEGA328P-AU") (pin "30") (pinfunction "PD0_30") (pintype "bidirectional"))
      (node (ref "R8") (pin "2") (pinfunction "2_2") (pintype "passive"))
    )
    (net (code "64") (name "TX-O_P") (class "Default")
      (node (ref "ATMEGA328P-AU") (pin "31") (pinfunction "PD1_31") (pintype "bidirectional"))
      (node (ref "R9") (pin "2") (pinfunction "2_2") (pintype "passive"))
    )
    (net (code "65") (name "TXLED") (class "Default")
      (node (ref "FTDI231XS1") (pin "10") (pinfunction "CBUS2_10") (pintype "bidirectional"))
      (node (ref "LED5") (pin "C") (pinfunction "C_C") (pintype "passive"))
    )
    (net (code "66") (name "VIN") (class "Default")
      (node (ref "5VREG") (pin "1") (pinfunction "IN_1") (pintype "input"))
      (node (ref "C15") (pin "A") (pinfunction "+_A") (pintype "passive"))
      (node (ref "D5") (pin "3") (pinfunction "C_3") (pintype "passive"))
    )
    (net (code "67") (name "VUSB") (class "Default")
      (node (ref "C11") (pin "A") (pinfunction "+_A") (pintype "passive"))
      (node (ref "C5") (pin "1") (pinfunction "1_1") (pintype "passive"))
      (node (ref "FB3") (pin "1") (pinfunction "1_1") (pintype "passive"))
      (node (ref "FB3") (pin "2") (pinfunction "2_2") (pintype "passive"))
      (node (ref "FTDI231XS1") (pin "15") (pinfunction "VCC_15") (pintype "bidirectional"))
      (node (ref "J2") (pin "VCC") (pinfunction "VBUS_VCC") (pintype "power_in"))
    )
    (net (code "68") (name "unconnected-(FTDI231XS1-CBUS0-Pad18)") (class "Default")
      (node (ref "FTDI231XS1") (pin "18") (pinfunction "CBUS0_18") (pintype "bidirectional"))
    )
    (net (code "69") (name "unconnected-(FTDI231XS1-CBUS3-Pad19)") (class "Default")
      (node (ref "FTDI231XS1") (pin "19") (pinfunction "CBUS3_19") (pintype "bidirectional"))
    )
    (net (code "70") (name "unconnected-(FTDI231XS1-~{CTS}-Pad9)") (class "Default")
      (node (ref "FTDI231XS1") (pin "9") (pinfunction "~{CTS}_9") (pintype "bidirectional"))
    )
    (net (code "71") (name "unconnected-(FTDI231XS1-~{DCD}-Pad8)") (class "Default")
      (node (ref "FTDI231XS1") (pin "8") (pinfunction "~{DCD}_8") (pintype "bidirectional"))
    )
    (net (code "72") (name "unconnected-(FTDI231XS1-~{DSR}-Pad7)") (class "Default")
      (node (ref "FTDI231XS1") (pin "7") (pinfunction "~{DSR}_7") (pintype "bidirectional"))
    )
    (net (code "73") (name "unconnected-(FTDI231XS1-~{RI}-Pad5)") (class "Default")
      (node (ref "FTDI231XS1") (pin "5") (pinfunction "~{RI}_5") (pintype "bidirectional"))
    )
    (net (code "74") (name "unconnected-(FTDI231XS1-~{RTS}-Pad2)") (class "Default")
      (node (ref "FTDI231XS1") (pin "2") (pinfunction "~{RTS}_2") (pintype "bidirectional"))
    )
    (net (code "75") (name "unconnected-(J1-Pad1)") (class "Default")
      (node (ref "J1") (pin "1") (pinfunction "1_1") (pintype "passive"))
    )
    (net (code "76") (name "unconnected-(J1-Pad2)") (class "Default")
      (node (ref "J1") (pin "2") (pinfunction "2_2") (pintype "passive"))
    )
    (net (code "77") (name "unconnected-(J1-Pad3)") (class "Default")
      (node (ref "J1") (pin "3") (pinfunction "3_3") (pintype "passive"))
    )
    (net (code "78") (name "unconnected-(J2-PadID)") (class "Default")
      (node (ref "J2") (pin "ID") (pinfunction "ID_ID") (pintype "bidirectional"))
    )
    (net (code "79") (name "unconnected-(J8-Pad2)") (class "Default")
      (node (ref "J8") (pin "2") (pinfunction "2_2") (pintype "passive"))
    )
    (net (code "80") (name "unconnected-(J8-Pad3)") (class "Default")
      (node (ref "J8") (pin "3") (pinfunction "3_3") (pintype "passive"))
    )
    (net (code "81") (name "unconnected-(J8-Pad13)") (class "Default")
      (node (ref "J8") (pin "13") (pinfunction "13_13") (pintype "passive"))
    )
    (net (code "82") (name "unconnected-(J8-Pad14)") (class "Default")
      (node (ref "J8") (pin "14") (pinfunction "14_14") (pintype "passive"))
    )
    (net (code "83") (name "unconnected-(J8-Pad15)") (class "Default")
      (node (ref "J8") (pin "15") (pinfunction "15_15") (pintype "passive"))
    )
    (net (code "84") (name "unconnected-(MPU6050-AUX_CL-Pad7)") (class "Default")
      (node (ref "MPU6050") (pin "7") (pinfunction "AUX_CL_7") (pintype "bidirectional"))
    )
    (net (code "85") (name "unconnected-(MPU6050-AUX_DA-Pad6)") (class "Default")
      (node (ref "MPU6050") (pin "6") (pinfunction "AUX_DA_6") (pintype "bidirectional"))
    )
    (net (code "86") (name "unconnected-(MPU6050-CLKIN-Pad1)") (class "Default")
      (node (ref "MPU6050") (pin "1") (pinfunction "CLKIN_1") (pintype "bidirectional"))
    )
    (net (code "87") (name "unconnected-(MPU6050-FYSNC-Pad11)") (class "Default")
      (node (ref "MPU6050") (pin "11") (pinfunction "FYSNC_11") (pintype "bidirectional"))
    )
    (net (code "88") (name "unconnected-(U$2-CD{slash}DAT3-PadCD{slash}DAT3{slash}SS{slash}CS)") (class "Default")
      (node (ref "U$2") (pin "CD/DAT3/SS/CS") (pinfunction "CD/DAT3_CD/DAT3/SS/CS") (pintype "bidirectional"))
    )
    (net (code "89") (name "unconnected-(U$2-PadDAT2)") (class "Default")
      (node (ref "U$2") (pin "DAT2") (pinfunction "DAT2_DAT2") (pintype "bidirectional"))
    )
  )
)
